# MJ818_clone_-_all_driver_-_prod.net
KiCad netlist of a schematic drawn in EAGLE
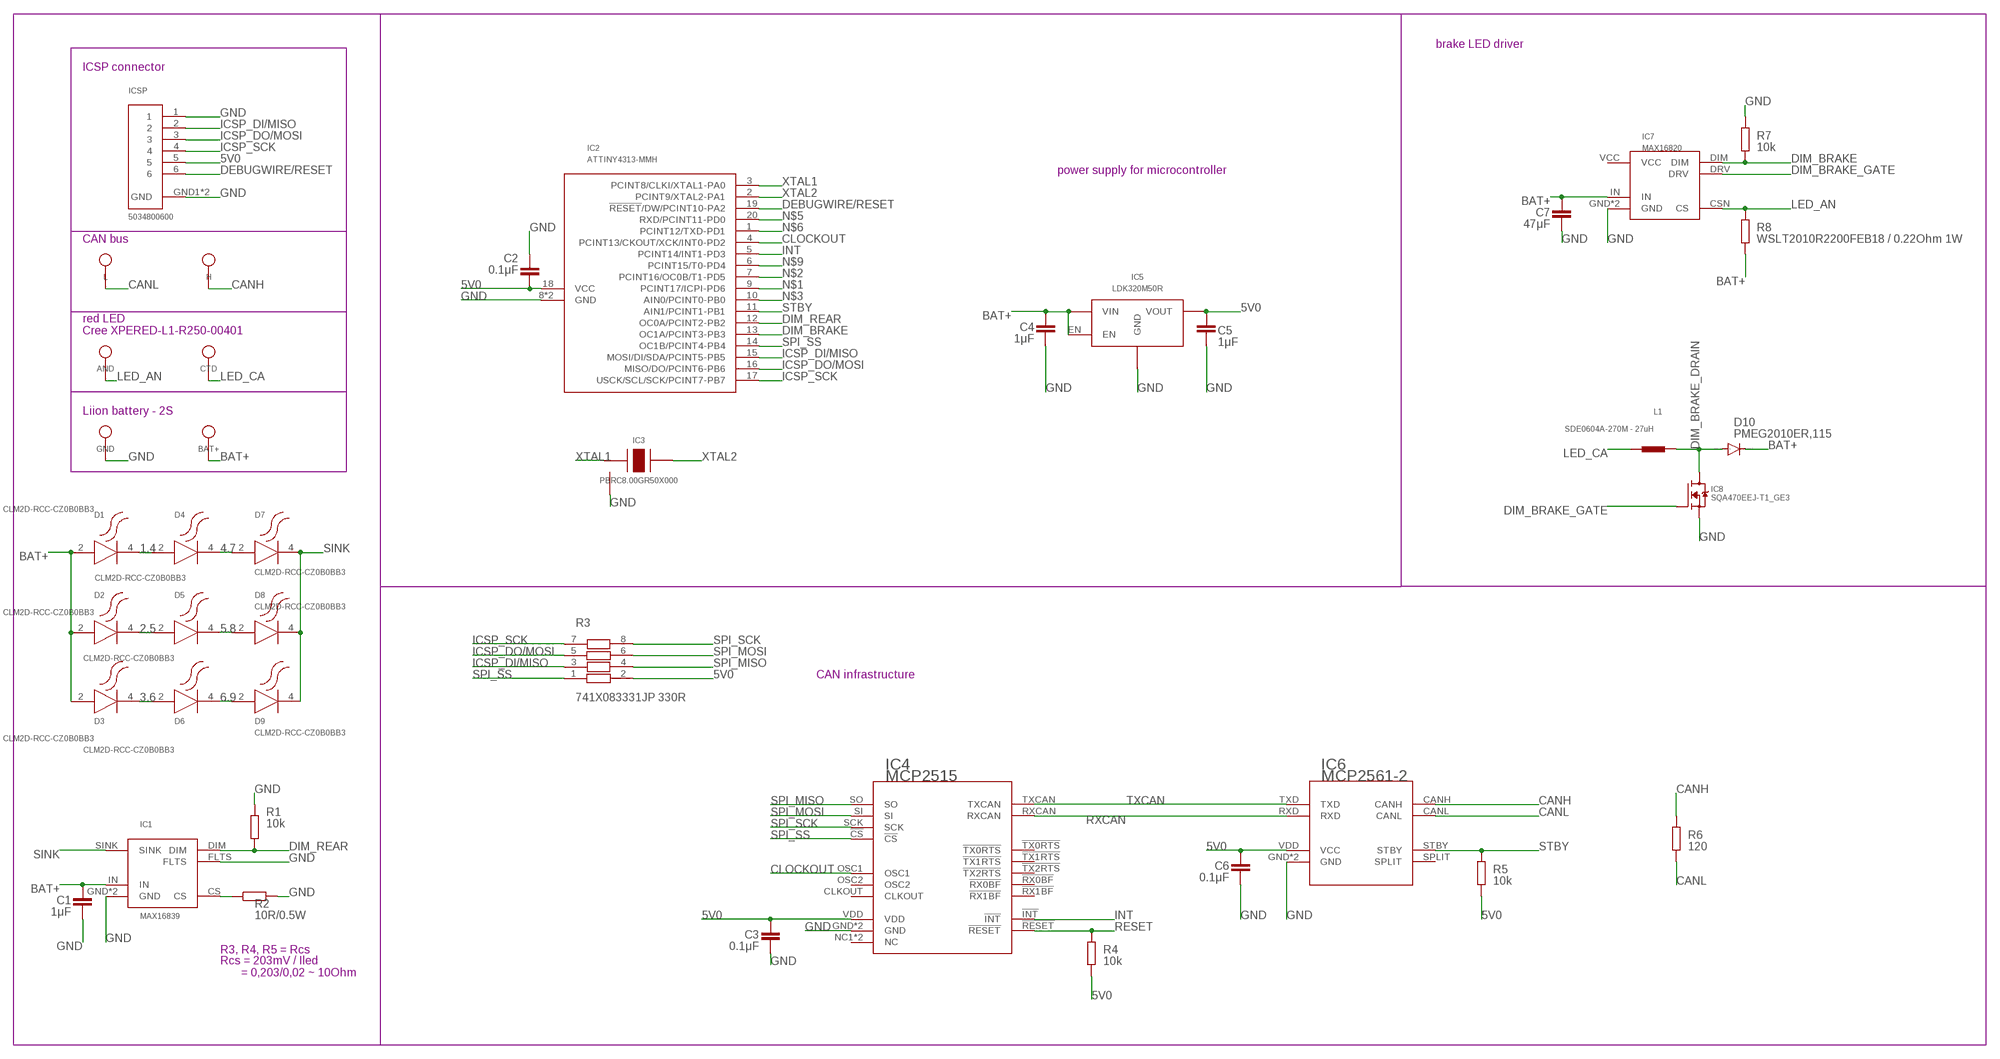
[diagram p0: schematic, sheet 1]

(export (version "E")
  (design (tool "Eeschema 10.0.6"))
  (components
    (comp (ref "AND")
      (value "LED anode")
      (footprint "eagle-import:SMT-1.2MM")
      (libsource (lib "eagle-import") (part "TPSMT-1.2MM"))
    )
    (comp (ref "BAT+")
      (value "bat+")
      (footprint "eagle-import:TH-0.9MM")
      (libsource (lib "eagle-import") (part "TPTH-0.9MM"))
    )
    (comp (ref "C1")
      (value "1μF")
      (footprint "eagle-import:C0402")
      (libsource (lib "eagle-import") (part "C-EUC0402"))
    )
    (comp (ref "C2")
      (value "0.1μF")
      (footprint "eagle-import:C0402")
      (libsource (lib "eagle-import") (part "C-EUC0402"))
    )
    (comp (ref "C3")
      (value "0.1μF")
      (footprint "eagle-import:C0402")
      (libsource (lib "eagle-import") (part "C-EUC0402"))
    )
    (comp (ref "C4")
      (value "1μF")
      (footprint "eagle-import:C0402")
      (libsource (lib "eagle-import") (part "C-EUC0402"))
    )
    (comp (ref "C5")
      (value "1μF")
      (footprint "eagle-import:C0402")
      (libsource (lib "eagle-import") (part "C-EUC0402"))
    )
    (comp (ref "C6")
      (value "0.1μF")
      (footprint "eagle-import:C0402")
      (libsource (lib "eagle-import") (part "C-EUC0402"))
    )
    (comp (ref "C7")
      (value "47μF")
      (footprint "eagle-import:C1206")
      (libsource (lib "eagle-import") (part "C-EUC1206"))
    )
    (comp (ref "CTD")
      (value "LED cathode")
      (footprint "eagle-import:SMT-1.2MM")
      (libsource (lib "eagle-import") (part "TPSMT-1.2MM"))
    )
    (comp (ref "D1")
      (value "CLM2D-RCC-CZ0B0BB3")
      (footprint "eagle-import:SMD")
      (libsource (lib "eagle-import") (part "1374-CLM2D-RCC-ACC-1064252"))
    )
    (comp (ref "D2")
      (value "CLM2D-RCC-CZ0B0BB3")
      (footprint "eagle-import:SMD")
      (libsource (lib "eagle-import") (part "1374-CLM2D-RCC-ACC-1064252"))
    )
    (comp (ref "D3")
      (value "CLM2D-RCC-CZ0B0BB3")
      (footprint "eagle-import:SMD")
      (libsource (lib "eagle-import") (part "1374-CLM2D-RCC-ACC-1064252"))
    )
    (comp (ref "D4")
      (value "CLM2D-RCC-CZ0B0BB3")
      (footprint "eagle-import:SMD")
      (libsource (lib "eagle-import") (part "1374-CLM2D-RCC-ACC-1064252"))
    )
    (comp (ref "D5")
      (value "CLM2D-RCC-CZ0B0BB3")
      (footprint "eagle-import:SMD")
      (libsource (lib "eagle-import") (part "1374-CLM2D-RCC-ACC-1064252"))
    )
    (comp (ref "D6")
      (value "CLM2D-RCC-CZ0B0BB3")
      (footprint "eagle-import:SMD")
      (libsource (lib "eagle-import") (part "1374-CLM2D-RCC-ACC-1064252"))
    )
    (comp (ref "D7")
      (value "CLM2D-RCC-CZ0B0BB3")
      (footprint "eagle-import:SMD")
      (libsource (lib "eagle-import") (part "1374-CLM2D-RCC-ACC-1064252"))
    )
    (comp (ref "D8")
      (value "CLM2D-RCC-CZ0B0BB3")
      (footprint "eagle-import:SMD")
      (libsource (lib "eagle-import") (part "1374-CLM2D-RCC-ACC-1064252"))
    )
    (comp (ref "D9")
      (value "CLM2D-RCC-CZ0B0BB3")
      (footprint "eagle-import:SMD")
      (libsource (lib "eagle-import") (part "1374-CLM2D-RCC-ACC-1064252"))
    )
    (comp (ref "D10")
      (value "PMEG2010ER,115")
      (footprint "eagle-import:SOD123")
      (libsource (lib "eagle-import") (part "DIODE-SOD123"))
    )
    (comp (ref "GND")
      (value "gnd")
      (footprint "eagle-import:TH-0.9MM")
      (libsource (lib "eagle-import") (part "TPTH-0.9MM"))
    )
    (comp (ref "H")
      (value "LED anode")
      (footprint "eagle-import:SMT-1.2MM")
      (libsource (lib "eagle-import") (part "TPSMT-1.2MM"))
    )
    (comp (ref "IC1")
      (value "MAX16839")
      (footprint "eagle-import:TDFN-6-EP")
      (libsource (lib "eagle-import") (part "MAX16839"))
    )
    (comp (ref "IC2")
      (value "ATTINY4313-MMH")
      (footprint "eagle-import:VQFN-20")
      (fields (field (name "SPICEPREFIX") "X"))
      (libsource (lib "eagle-import") (part "ATTINY4313VQFN-20"))
    )
    (comp (ref "IC3")
      (value "PBRC8.00GR50X000")
      (footprint "eagle-import:SMT")
      (libsource (lib "eagle-import") (part "PRQV"))
    )
    (comp (ref "IC4")
      (value "MCP2515")
      (footprint "eagle-import:QFN20")
      (libsource (lib "eagle-import") (part "MCP2515-I-ML"))
    )
    (comp (ref "IC5")
      (value "LDK320M50R")
      (footprint "eagle-import:SOT-23-5L")
      (libsource (lib "eagle-import") (part "LDK320SOT-23-5L"))
    )
    (comp (ref "IC6")
      (value "MCP2561-2")
      (footprint "eagle-import:DFN10")
      (libsource (lib "eagle-import") (part "MCP2561-2"))
    )
    (comp (ref "IC7")
      (value "MAX16820")
      (footprint "eagle-import:TDFN-6-EP")
      (libsource (lib "eagle-import") (part "MAX16820"))
    )
    (comp (ref "IC8")
      (value "SQA470EEJ-T1_GE3")
      (footprint "eagle-import:SC-70-6")
      (libsource (lib "eagle-import") (part "SIA456DJ"))
    )
    (comp (ref "ICSP")
      (value "5034800600")
      (footprint "eagle-import:SMT")
      (libsource (lib "eagle-import") (part "5034800600"))
    )
    (comp (ref "L")
      (value "LED anode")
      (footprint "eagle-import:SMT-1.2MM")
      (libsource (lib "eagle-import") (part "TPSMT-1.2MM"))
    )
    (comp (ref "L1")
      (value "SDE0604A-270M - 27uH")
      (footprint "eagle-import:SMT")
      (libsource (lib "eagle-import") (part "DE0604A-778075"))
    )
    (comp (ref "R1")
      (value "10k")
      (footprint "eagle-import:R0402")
      (libsource (lib "eagle-import") (part "R-EU_R0402"))
    )
    (comp (ref "R2")
      (value "10R/0.5W")
      (footprint "eagle-import:R0603")
      (libsource (lib "eagle-import") (part "R-EU_R0603"))
    )
    (comp (ref "R3")
      (value "741X083331JP 330R")
      (footprint "eagle-import:0402")
      (libsource (lib "eagle-import") (part "741X083331JP"))
    )
    (comp (ref "R4")
      (value "10k")
      (footprint "eagle-import:R0402")
      (libsource (lib "eagle-import") (part "R-EU_R0402"))
    )
    (comp (ref "R5")
      (value "10k")
      (footprint "eagle-import:R0402")
      (libsource (lib "eagle-import") (part "R-EU_R0402"))
    )
    (comp (ref "R6")
      (value "120")
      (footprint "eagle-import:R0805")
      (libsource (lib "eagle-import") (part "R-EU_R0805"))
    )
    (comp (ref "R7")
      (value "10k")
      (footprint "eagle-import:R0402")
      (libsource (lib "eagle-import") (part "R-EU_R0402"))
    )
    (comp (ref "R8")
      (value "WSLT2010R2200FEB18 / 0.22Ohm 1W")
      (footprint "eagle-import:R2010")
      (libsource (lib "eagle-import") (part "R-EU_R2010"))
    )
  )
  (nets
    (net (code "1") (name "/1.4") (class "Default")
      (node (ref "D1") (pin "4") (pinfunction "C_4") (pintype "bidirectional"))
      (node (ref "D4") (pin "2") (pinfunction "A_2") (pintype "bidirectional"))
    )
    (net (code "2") (name "/2.5") (class "Default")
      (node (ref "D2") (pin "4") (pinfunction "C_4") (pintype "bidirectional"))
      (node (ref "D5") (pin "2") (pinfunction "A_2") (pintype "bidirectional"))
    )
    (net (code "3") (name "/3.6") (class "Default")
      (node (ref "D3") (pin "4") (pinfunction "C_4") (pintype "bidirectional"))
      (node (ref "D6") (pin "2") (pinfunction "A_2") (pintype "bidirectional"))
    )
    (net (code "4") (name "/4.7") (class "Default")
      (node (ref "D4") (pin "4") (pinfunction "C_4") (pintype "bidirectional"))
      (node (ref "D7") (pin "2") (pinfunction "A_2") (pintype "bidirectional"))
    )
    (net (code "5") (name "/5.8") (class "Default")
      (node (ref "D5") (pin "4") (pinfunction "C_4") (pintype "bidirectional"))
      (node (ref "D8") (pin "2") (pinfunction "A_2") (pintype "bidirectional"))
    )
    (net (code "6") (name "/5V0") (class "Default")
      (node (ref "C2") (pin "1") (pinfunction "1_1") (pintype "passive"))
      (node (ref "C3") (pin "1") (pinfunction "1_1") (pintype "passive"))
      (node (ref "C5") (pin "2") (pinfunction "2_2") (pintype "passive"))
      (node (ref "C6") (pin "1") (pinfunction "1_1") (pintype "passive"))
      (node (ref "IC2") (pin "18") (pinfunction "VCC_18") (pintype "bidirectional"))
      (node (ref "IC4") (pin "VDD") (pinfunction "VDD_VDD") (pintype "power_in"))
      (node (ref "IC5") (pin "OUT") (pinfunction "VOUT_OUT") (pintype "bidirectional"))
      (node (ref "IC6") (pin "VDD") (pinfunction "VCC_VDD") (pintype "power_in"))
      (node (ref "ICSP") (pin "5") (pinfunction "5_5") (pintype "bidirectional"))
      (node (ref "R3") (pin "2") (pinfunction "2_2") (pintype "bidirectional"))
      (node (ref "R4") (pin "1") (pinfunction "1_1") (pintype "passive"))
      (node (ref "R5") (pin "1") (pinfunction "1_1") (pintype "passive"))
    )
    (net (code "7") (name "/6.9") (class "Default")
      (node (ref "D6") (pin "4") (pinfunction "C_4") (pintype "bidirectional"))
      (node (ref "D9") (pin "2") (pinfunction "A_2") (pintype "bidirectional"))
    )
    (net (code "8") (name "/BAT+") (class "Default")
      (node (ref "BAT+") (pin "TP$1") (pinfunction "TP$1_TP$1") (pintype "bidirectional"))
      (node (ref "C1") (pin "2") (pinfunction "2_2") (pintype "passive"))
      (node (ref "C4") (pin "1") (pinfunction "1_1") (pintype "passive"))
      (node (ref "C7") (pin "1") (pinfunction "1_1") (pintype "passive"))
      (node (ref "D1") (pin "2") (pinfunction "A_2") (pintype "bidirectional"))
      (node (ref "D10") (pin "C") (pinfunction "C_C") (pintype "passive"))
      (node (ref "D2") (pin "2") (pinfunction "A_2") (pintype "bidirectional"))
      (node (ref "D3") (pin "2") (pinfunction "A_2") (pintype "bidirectional"))
      (node (ref "IC1") (pin "IN") (pinfunction "IN_IN") (pintype "power_in"))
      (node (ref "IC5") (pin "EN") (pinfunction "EN_EN") (pintype "bidirectional"))
      (node (ref "IC5") (pin "IN") (pinfunction "VIN_IN") (pintype "bidirectional"))
      (node (ref "IC7") (pin "IN") (pinfunction "IN_IN") (pintype "power_in"))
      (node (ref "R8") (pin "2") (pinfunction "2_2") (pintype "passive"))
    )
    (net (code "9") (name "/CANH") (class "Default")
      (node (ref "H") (pin "P$1") (pinfunction "TP$1_P$1") (pintype "bidirectional"))
      (node (ref "IC6") (pin "CANH") (pinfunction "CANH_CANH") (pintype "bidirectional"))
      (node (ref "R6") (pin "2") (pinfunction "2_2") (pintype "passive"))
    )
    (net (code "10") (name "/CANL") (class "Default")
      (node (ref "IC6") (pin "CANL") (pinfunction "CANL_CANL") (pintype "bidirectional"))
      (node (ref "L") (pin "P$1") (pinfunction "TP$1_P$1") (pintype "bidirectional"))
      (node (ref "R6") (pin "1") (pinfunction "1_1") (pintype "passive"))
    )
    (net (code "11") (name "/CLOCKOUT") (class "Default")
      (node (ref "IC2") (pin "4") (pinfunction "PCINT13/CKOUT/XCK/INT0-PD2_4") (pintype "bidirectional"))
      (node (ref "IC4") (pin "OSC1") (pinfunction "OSC1_OSC1") (pintype "bidirectional"))
    )
    (net (code "12") (name "/DEBUGWIRE{slash}RESET") (class "Default")
      (node (ref "IC2") (pin "19") (pinfunction "~{RESET}/DW/PCINT10-PA2_19") (pintype "bidirectional"))
      (node (ref "ICSP") (pin "6") (pinfunction "6_6") (pintype "bidirectional"))
    )
    (net (code "13") (name "/DIM_BRAKE") (class "Default")
      (node (ref "IC2") (pin "13") (pinfunction "OC1A/PCINT3-PB3_13") (pintype "bidirectional"))
      (node (ref "IC7") (pin "DIM") (pinfunction "DIM_DIM") (pintype "bidirectional"))
      (node (ref "R7") (pin "1") (pinfunction "1_1") (pintype "passive"))
    )
    (net (code "14") (name "/DIM_BRAKE_DRAIN") (class "Default")
      (node (ref "D10") (pin "A") (pinfunction "A_A") (pintype "passive"))
      (node (ref "IC8") (pin "1D") (pinfunction "D_1D") (pintype "passive"))
      (node (ref "IC8") (pin "2D") (pinfunction "D_2D") (pintype "passive"))
      (node (ref "IC8") (pin "5D") (pinfunction "D_5D") (pintype "passive"))
      (node (ref "IC8") (pin "6D") (pinfunction "D_6D") (pintype "passive"))
      (node (ref "IC8") (pin "D") (pinfunction "D_D") (pintype "passive"))
      (node (ref "L1") (pin "P$2") (pinfunction "P$2_P$2") (pintype "bidirectional"))
    )
    (net (code "15") (name "/DIM_BRAKE_GATE") (class "Default")
      (node (ref "IC7") (pin "DRV") (pinfunction "DRV_DRV") (pintype "bidirectional"))
      (node (ref "IC8") (pin "3G") (pinfunction "G_3G") (pintype "passive"))
    )
    (net (code "16") (name "/DIM_REAR") (class "Default")
      (node (ref "IC1") (pin "DIM") (pinfunction "DIM_DIM") (pintype "bidirectional"))
      (node (ref "IC2") (pin "12") (pinfunction "OC0A/PCINT2-PB2_12") (pintype "bidirectional"))
      (node (ref "R1") (pin "1") (pinfunction "1_1") (pintype "passive"))
    )
    (net (code "17") (name "/GND") (class "Default")
      (node (ref "C1") (pin "1") (pinfunction "1_1") (pintype "passive"))
      (node (ref "C2") (pin "2") (pinfunction "2_2") (pintype "passive"))
      (node (ref "C3") (pin "2") (pinfunction "2_2") (pintype "passive"))
      (node (ref "C4") (pin "2") (pinfunction "2_2") (pintype "passive"))
      (node (ref "C5") (pin "1") (pinfunction "1_1") (pintype "passive"))
      (node (ref "C6") (pin "2") (pinfunction "2_2") (pintype "passive"))
      (node (ref "C7") (pin "2") (pinfunction "2_2") (pintype "passive"))
      (node (ref "GND") (pin "TP$1") (pinfunction "TP$1_TP$1") (pintype "bidirectional"))
      (node (ref "IC1") (pin "FLTS") (pinfunction "FLTS_FLTS") (pintype "bidirectional"))
      (node (ref "IC1") (pin "GND") (pinfunction "GND_GND") (pintype "power_in"))
      (node (ref "IC1") (pin "GND1") (pinfunction "GND_GND1") (pintype "power_in"))
      (node (ref "IC2") (pin "8") (pinfunction "GND_8") (pintype "bidirectional"))
      (node (ref "IC2") (pin "GND") (pinfunction "GND_GND") (pintype "bidirectional"))
      (node (ref "IC3") (pin "GND") (pinfunction "GND_GND") (pintype "bidirectional"))
      (node (ref "IC4") (pin "GND") (pinfunction "GND_GND") (pintype "power_in"))
      (node (ref "IC4") (pin "GND6") (pinfunction "GND_GND6") (pintype "power_in"))
      (node (ref "IC5") (pin "GND") (pinfunction "GND_GND") (pintype "bidirectional"))
      (node (ref "IC6") (pin "GND") (pinfunction "GND_GND") (pintype "power_in"))
      (node (ref "IC6") (pin "VSS") (pinfunction "GND_VSS") (pintype "power_in"))
      (node (ref "IC7") (pin "GND") (pinfunction "GND_GND") (pintype "power_in"))
      (node (ref "IC7") (pin "GND1") (pinfunction "GND_GND1") (pintype "power_in"))
      (node (ref "IC8") (pin "4S") (pinfunction "S_4S") (pintype "passive"))
      (node (ref "IC8") (pin "S") (pinfunction "S_S") (pintype "passive"))
      (node (ref "ICSP") (pin "1") (pinfunction "1_1") (pintype "bidirectional"))
      (node (ref "ICSP") (pin "GND1") (pinfunction "GND_GND1") (pintype "bidirectional"))
      (node (ref "ICSP") (pin "GND2") (pinfunction "GND_GND2") (pintype "bidirectional"))
      (node (ref "R1") (pin "2") (pinfunction "2_2") (pintype "passive"))
      (node (ref "R2") (pin "2") (pinfunction "2_2") (pintype "passive"))
      (node (ref "R7") (pin "2") (pinfunction "2_2") (pintype "passive"))
    )
    (net (code "18") (name "/ICSP_DI{slash}MISO") (class "Default")
      (node (ref "IC2") (pin "15") (pinfunction "MOSI/DI/SDA/PCINT5-PB5_15") (pintype "bidirectional"))
      (node (ref "ICSP") (pin "2") (pinfunction "2_2") (pintype "bidirectional"))
      (node (ref "R3") (pin "3") (pinfunction "3_3") (pintype "bidirectional"))
    )
    (net (code "19") (name "/ICSP_DO{slash}MOSI") (class "Default")
      (node (ref "IC2") (pin "16") (pinfunction "MISO/DO/PCINT6-PB6_16") (pintype "bidirectional"))
      (node (ref "ICSP") (pin "3") (pinfunction "3_3") (pintype "bidirectional"))
      (node (ref "R3") (pin "5") (pinfunction "5_5") (pintype "bidirectional"))
    )
    (net (code "20") (name "/ICSP_SCK") (class "Default")
      (node (ref "IC2") (pin "17") (pinfunction "USCK/SCL/SCK/PCINT7-PB7_17") (pintype "bidirectional"))
      (node (ref "ICSP") (pin "4") (pinfunction "4_4") (pintype "bidirectional"))
      (node (ref "R3") (pin "7") (pinfunction "7_7") (pintype "bidirectional"))
    )
    (net (code "21") (name "/INT") (class "Default")
      (node (ref "IC2") (pin "5") (pinfunction "PCINT14/INT1-PD3_5") (pintype "bidirectional"))
      (node (ref "IC4") (pin "!INT!") (pinfunction "~{INT}_!INT!") (pintype "bidirectional"))
    )
    (net (code "22") (name "/LED_AN") (class "Default")
      (node (ref "AND") (pin "P$1") (pinfunction "TP$1_P$1") (pintype "bidirectional"))
      (node (ref "IC7") (pin "CSN") (pinfunction "CS_CSN") (pintype "bidirectional"))
      (node (ref "R8") (pin "1") (pinfunction "1_1") (pintype "passive"))
    )
    (net (code "23") (name "/LED_CA") (class "Default")
      (node (ref "CTD") (pin "P$1") (pinfunction "TP$1_P$1") (pintype "bidirectional"))
      (node (ref "L1") (pin "P$1") (pinfunction "P$1_P$1") (pintype "bidirectional"))
    )
    (net (code "24") (name "/N$1") (class "Default")
      (node (ref "IC2") (pin "9") (pinfunction "PCINT17/ICPI-PD6_9") (pintype "bidirectional"))
    )
    (net (code "25") (name "/N$2") (class "Default")
      (node (ref "IC2") (pin "7") (pinfunction "PCINT16/OC0B/T1-PD5_7") (pintype "bidirectional"))
    )
    (net (code "26") (name "/N$3") (class "Default")
      (node (ref "IC2") (pin "10") (pinfunction "AIN0/PCINT0-PB0_10") (pintype "bidirectional"))
    )
    (net (code "27") (name "/N$5") (class "Default")
      (node (ref "IC2") (pin "20") (pinfunction "RXD/PCINT11-PD0_20") (pintype "bidirectional"))
    )
    (net (code "28") (name "/N$6") (class "Default")
      (node (ref "IC2") (pin "1") (pinfunction "PCINT12/TXD-PD1_1") (pintype "bidirectional"))
    )
    (net (code "29") (name "/N$9") (class "Default")
      (node (ref "IC2") (pin "6") (pinfunction "PCINT15/T0-PD4_6") (pintype "bidirectional"))
    )
    (net (code "30") (name "/RESET") (class "Default")
      (node (ref "IC4") (pin "!RESET!") (pinfunction "~{RESET}_!RESET!") (pintype "bidirectional"))
      (node (ref "R4") (pin "2") (pinfunction "2_2") (pintype "passive"))
    )
    (net (code "31") (name "/RXCAN") (class "Default")
      (node (ref "IC4") (pin "RXCAN") (pinfunction "RXCAN_RXCAN") (pintype "input"))
      (node (ref "IC6") (pin "RXD") (pinfunction "RXD_RXD") (pintype "output"))
    )
    (net (code "32") (name "/SINK") (class "Default")
      (node (ref "D7") (pin "4") (pinfunction "C_4") (pintype "bidirectional"))
      (node (ref "D8") (pin "4") (pinfunction "C_4") (pintype "bidirectional"))
      (node (ref "D9") (pin "4") (pinfunction "C_4") (pintype "bidirectional"))
      (node (ref "IC1") (pin "SINK") (pinfunction "SINK_SINK") (pintype "power_in"))
    )
    (net (code "33") (name "/SPI_MISO") (class "Default")
      (node (ref "IC4") (pin "SO") (pinfunction "SO_SO") (pintype "output"))
      (node (ref "R3") (pin "4") (pinfunction "4_4") (pintype "bidirectional"))
    )
    (net (code "34") (name "/SPI_MOSI") (class "Default")
      (node (ref "IC4") (pin "SI") (pinfunction "SI_SI") (pintype "input"))
      (node (ref "R3") (pin "6") (pinfunction "6_6") (pintype "bidirectional"))
    )
    (net (code "35") (name "/SPI_SCK") (class "Default")
      (node (ref "IC4") (pin "SCK") (pinfunction "SCK_SCK") (pintype "bidirectional"))
      (node (ref "R3") (pin "8") (pinfunction "8_8") (pintype "bidirectional"))
    )
    (net (code "36") (name "/SPI_SS") (class "Default")
      (node (ref "IC2") (pin "14") (pinfunction "OC1B/PCINT4-PB4_14") (pintype "bidirectional"))
      (node (ref "IC4") (pin "!CS!") (pinfunction "~{CS}_!CS!") (pintype "bidirectional"))
      (node (ref "R3") (pin "1") (pinfunction "1_1") (pintype "bidirectional"))
    )
    (net (code "37") (name "/STBY") (class "Default")
      (node (ref "IC2") (pin "11") (pinfunction "AIN1/PCINT1-PB1_11") (pintype "bidirectional"))
      (node (ref "IC6") (pin "STBY") (pinfunction "STBY_STBY") (pintype "bidirectional"))
      (node (ref "R5") (pin "2") (pinfunction "2_2") (pintype "passive"))
    )
    (net (code "38") (name "/TXCAN") (class "Default")
      (node (ref "IC4") (pin "TXCAN") (pinfunction "TXCAN_TXCAN") (pintype "output"))
      (node (ref "IC6") (pin "TXD") (pinfunction "TXD_TXD") (pintype "input"))
    )
    (net (code "39") (name "/VCC") (class "Default")
      (node (ref "IC7") (pin "VCC") (pinfunction "VCC_VCC") (pintype "power_in"))
    )
    (net (code "40") (name "/XTAL1") (class "Default")
      (node (ref "IC2") (pin "3") (pinfunction "PCINT8/CLKI/XTAL1-PA0_3") (pintype "bidirectional"))
      (node (ref "IC3") (pin "XTAL1") (pinfunction "XTAL1_XTAL1") (pintype "bidirectional"))
    )
    (net (code "41") (name "/XTAL2") (class "Default")
      (node (ref "IC2") (pin "2") (pinfunction "PCINT9/XTAL2-PA1_2") (pintype "bidirectional"))
      (node (ref "IC3") (pin "XTAL2") (pinfunction "XTAL2_XTAL2") (pintype "bidirectional"))
    )
    (net (code "42") (name "Net-(IC1-PadCS)") (class "Default")
      (node (ref "IC1") (pin "CS") (pinfunction "CS_CS") (pintype "bidirectional"))
      (node (ref "R2") (pin "1") (pinfunction "1_1") (pintype "passive"))
    )
    (net (code "43") (name "unconnected-(IC4-NC-PadNC1)") (class "Default")
      (node (ref "IC4") (pin "NC1") (pinfunction "NC_NC1") (pintype "no_connect"))
    )
    (net (code "44") (name "unconnected-(IC4-NC-PadNC2)") (class "Default")
      (node (ref "IC4") (pin "NC2") (pinfunction "NC_NC2") (pintype "no_connect"))
    )
    (net (code "45") (name "unconnected-(IC4-PadCLKOUT)") (class "Default")
      (node (ref "IC4") (pin "CLKOUT") (pinfunction "CLKOUT_CLKOUT") (pintype "bidirectional"))
    )
    (net (code "46") (name "unconnected-(IC4-PadOSC2)") (class "Default")
      (node (ref "IC4") (pin "OSC2") (pinfunction "OSC2_OSC2") (pintype "bidirectional"))
    )
    (net (code "47") (name "unconnected-(IC4-~{RX0BF}-Pad!RX0BF!)") (class "Default")
      (node (ref "IC4") (pin "!RX0BF!") (pinfunction "~{RX0BF}_!RX0BF!") (pintype "bidirectional"))
    )
    (net (code "48") (name "unconnected-(IC4-~{RX1BF}-Pad!RX1BF!)") (class "Default")
      (node (ref "IC4") (pin "!RX1BF!") (pinfunction "~{RX1BF}_!RX1BF!") (pintype "bidirectional"))
    )
    (net (code "49") (name "unconnected-(IC4-~{TX0RTS}-Pad!TX0RTS!)") (class "Default")
      (node (ref "IC4") (pin "!TX0RTS!") (pinfunction "~{TX0RTS}_!TX0RTS!") (pintype "bidirectional"))
    )
    (net (code "50") (name "unconnected-(IC4-~{TX1RTS}-Pad!TX1RTS!)") (class "Default")
      (node (ref "IC4") (pin "!TX1RTS!") (pinfunction "~{TX1RTS}_!TX1RTS!") (pintype "bidirectional"))
    )
    (net (code "51") (name "unconnected-(IC4-~{TX2RTS}-Pad!TX2RTS!)") (class "Default")
      (node (ref "IC4") (pin "!TX2RTS!") (pinfunction "~{TX2RTS}_!TX2RTS!") (pintype "bidirectional"))
    )
    (net (code "52") (name "unconnected-(IC6-PadSPLIT)") (class "Default")
      (node (ref "IC6") (pin "SPLIT") (pinfunction "SPLIT_SPLIT") (pintype "bidirectional"))
    )
  )
)
